# Probe_Board.net
KiCad netlist of a schematic drawn in EAGLE
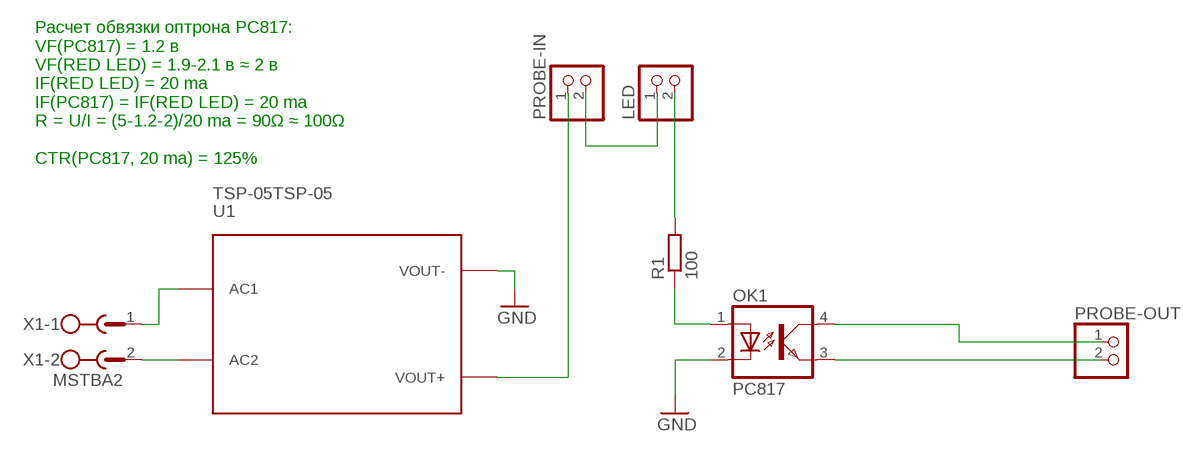
[diagram p0: schematic, sheet 1]

(export (version "E")
  (design (tool "Eeschema 10.0.6"))
  (components
    (comp (ref "LED")
      (value "PINHD-1X2/90")
      (footprint "eagle-import:1X02_90")
      (libsource (lib "eagle-import") (part "PINHD-1X2/90"))
    )
    (comp (ref "OK1")
      (value "PC817")
      (footprint "eagle-import:DIL04")
      (fields (field (name "MPN") "PC817X4J000F"))
      (libsource (lib "eagle-import") (part "PC817"))
    )
    (comp (ref "PROBE-IN")
      (value "PINHD-1X2/90")
      (footprint "eagle-import:1X02_90")
      (libsource (lib "eagle-import") (part "PINHD-1X2/90"))
    )
    (comp (ref "PROBE-OUT")
      (value "PINHD-1X2/90")
      (footprint "eagle-import:1X02_90")
      (libsource (lib "eagle-import") (part "PINHD-1X2/90"))
    )
    (comp (ref "R1")
      (value "100")
      (footprint "eagle-import:0207_12")
      (libsource (lib "eagle-import") (part "R-EU_0207/12"))
    )
    (comp (ref "U1")
      (value "TSP-05TSP-05")
      (footprint "eagle-import:TSP-05")
      (libsource (lib "eagle-import") (part "TSP-05TSP-05"))
    )
    (comp (ref "X1")
      (value "MSTBA2")
      (footprint "eagle-import:MSTBA2")
      (libsource (lib "eagle-import") (part "MSTBA2"))
    )
  )
  (nets
    (net (code "1") (name "GND") (class "Default")
      (node (ref "OK1") (pin "2") (pinfunction "C_2") (pintype "passive"))
      (node (ref "U1") (pin "P$3") (pinfunction "VOUT-_P$3") (pintype "power_in"))
    )
    (net (code "2") (name "Net-(LED-Pad1)") (class "Default")
      (node (ref "LED") (pin "1") (pinfunction "1_1") (pintype "passive"))
      (node (ref "PROBE-IN") (pin "2") (pinfunction "2_2") (pintype "passive"))
    )
    (net (code "3") (name "Net-(LED-Pad2)") (class "Default")
      (node (ref "LED") (pin "2") (pinfunction "2_2") (pintype "passive"))
      (node (ref "R1") (pin "2") (pinfunction "2_2") (pintype "passive"))
    )
    (net (code "4") (name "Net-(OK1-A)") (class "Default")
      (node (ref "OK1") (pin "1") (pinfunction "A_1") (pintype "passive"))
      (node (ref "R1") (pin "1") (pinfunction "1_1") (pintype "passive"))
    )
    (net (code "5") (name "Net-(OK1-COL)") (class "Default")
      (node (ref "OK1") (pin "4") (pinfunction "COL_4") (pintype "passive"))
      (node (ref "PROBE-OUT") (pin "1") (pinfunction "1_1") (pintype "passive"))
    )
    (net (code "6") (name "Net-(OK1-EMIT)") (class "Default")
      (node (ref "OK1") (pin "3") (pinfunction "EMIT_3") (pintype "passive"))
      (node (ref "PROBE-OUT") (pin "2") (pinfunction "2_2") (pintype "passive"))
    )
    (net (code "7") (name "Net-(U1-AC1)") (class "Default")
      (node (ref "U1") (pin "P$1") (pinfunction "AC1_P$1") (pintype "power_in"))
      (node (ref "X1") (pin "1") (pinfunction "1_1") (pintype "passive"))
    )
    (net (code "8") (name "Net-(U1-AC2)") (class "Default")
      (node (ref "U1") (pin "P$2") (pinfunction "AC2_P$2") (pintype "power_in"))
      (node (ref "X1") (pin "2") (pinfunction "1_2") (pintype "passive"))
    )
    (net (code "9") (name "Net-(U1-VOUT+)") (class "Default")
      (node (ref "PROBE-IN") (pin "1") (pinfunction "1_1") (pintype "passive"))
      (node (ref "U1") (pin "P$4") (pinfunction "VOUT+_P$4") (pintype "power_in"))
    )
  )
)
